# Lipo-Charger-12V-setup.net
KiCad netlist of a schematic drawn in EAGLE
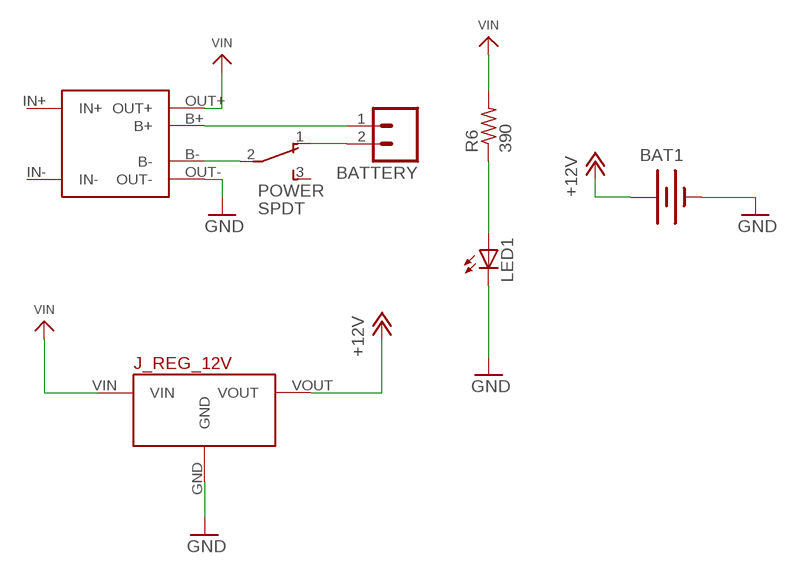
[diagram p0: schematic, sheet 1]

(export (version "E")
  (design (tool "Eeschema 10.0.6"))
  (components
    (comp (ref "BAT1")
      (value "BATTERYA23")
      (footprint "eagle-import:BATTERY-A23")
      (libsource (lib "eagle-import") (part "BATTERYA23"))
    )
    (comp (ref "BATTERY")
      (value "M02LOCK")
      (footprint "eagle-import:1X02_LOCK")
      (libsource (lib "eagle-import") (part "M02LOCK"))
    )
    (comp (ref "J_REG_12V")
      (value "POLOLU_VOLTAGE_REGULATORS_3PIN")
      (footprint "eagle-import:POLOLU_5V-12V_STEPUP_U3V12F5-U3V12F12")
      (libsource (lib "eagle-import") (part "POLOLU_VOLTAGE_REGULATORS_3PIN"))
    )
    (comp (ref "LED1")
      (value "LED3MM")
      (footprint "eagle-import:LED3MM")
      (libsource (lib "eagle-import") (part "LED3MM"))
    )
    (comp (ref "POWER")
      (value "SPDT")
      (footprint "eagle-import:SWITCH_SPDT-TE-CONNECT")
      (libsource (lib "eagle-import") (part "SWITCH_SPDTTE-CONNECT"))
    )
    (comp (ref "R6")
      (value "390")
      (footprint "eagle-import:0204_7")
      (libsource (lib "eagle-import") (part "R-US_0204/7"))
    )
    (comp (ref "USB-LIPO-CHARGER")
      (value "TP4056-MODULE")
      (footprint "eagle-import:TP4056-LITHIUM-PROTECTED-MODULE")
      (libsource (lib "eagle-import") (part "TP4056-MODULE"))
    )
  )
  (nets
    (net (code "1") (name "+12V") (class "Default")
      (node (ref "BAT1") (pin "PWR@1") (pinfunction "+_PWR@1") (pintype "power_in"))
      (node (ref "J_REG_12V") (pin "VOUT") (pinfunction "VOUT_VOUT") (pintype "bidirectional"))
    )
    (net (code "2") (name "/IN+") (class "Default")
      (node (ref "USB-LIPO-CHARGER") (pin "IN+") (pinfunction "IN+_IN+") (pintype "power_in"))
    )
    (net (code "3") (name "/IN-") (class "Default")
      (node (ref "USB-LIPO-CHARGER") (pin "IN-") (pinfunction "IN-_IN-") (pintype "power_in"))
    )
    (net (code "4") (name "GND") (class "Default")
      (node (ref "BAT1") (pin "GND@1") (pinfunction "-_GND@1") (pintype "power_in"))
      (node (ref "J_REG_12V") (pin "GND") (pinfunction "GND_GND") (pintype "bidirectional"))
      (node (ref "LED1") (pin "K") (pinfunction "C_K") (pintype "passive"))
      (node (ref "USB-LIPO-CHARGER") (pin "OUT-") (pinfunction "OUT-_OUT-") (pintype "power_in"))
    )
    (net (code "5") (name "Net-(BATTERY-Pad1)") (class "Default")
      (node (ref "BATTERY") (pin "1") (pinfunction "1_1") (pintype "passive"))
      (node (ref "USB-LIPO-CHARGER") (pin "B+") (pinfunction "B+_B+") (pintype "power_in"))
    )
    (net (code "6") (name "Net-(BATTERY-Pad2)") (class "Default")
      (node (ref "BATTERY") (pin "2") (pinfunction "2_2") (pintype "passive"))
      (node (ref "POWER") (pin "1") (pinfunction "1_1") (pintype "passive"))
    )
    (net (code "7") (name "Net-(LED1-PadA)") (class "Default")
      (node (ref "LED1") (pin "A") (pinfunction "A_A") (pintype "passive"))
      (node (ref "R6") (pin "1") (pinfunction "1_1") (pintype "passive"))
    )
    (net (code "8") (name "Net-(POWER-Pad2)") (class "Default")
      (node (ref "POWER") (pin "2") (pinfunction "2_2") (pintype "passive"))
      (node (ref "USB-LIPO-CHARGER") (pin "B-") (pinfunction "B-_B-") (pintype "power_in"))
    )
    (net (code "9") (name "VIN") (class "Default")
      (node (ref "J_REG_12V") (pin "VIN") (pinfunction "VIN_VIN") (pintype "bidirectional"))
      (node (ref "R6") (pin "2") (pinfunction "2_2") (pintype "passive"))
      (node (ref "USB-LIPO-CHARGER") (pin "OUT+") (pinfunction "OUT+_OUT+") (pintype "power_in"))
    )
    (net (code "10") (name "unconnected-(POWER-Pad3)") (class "Default")
      (node (ref "POWER") (pin "3") (pinfunction "3_3") (pintype "passive"))
    )
  )
)
